# smarthome-agent-1.net
KiCad netlist of a schematic drawn in EAGLE
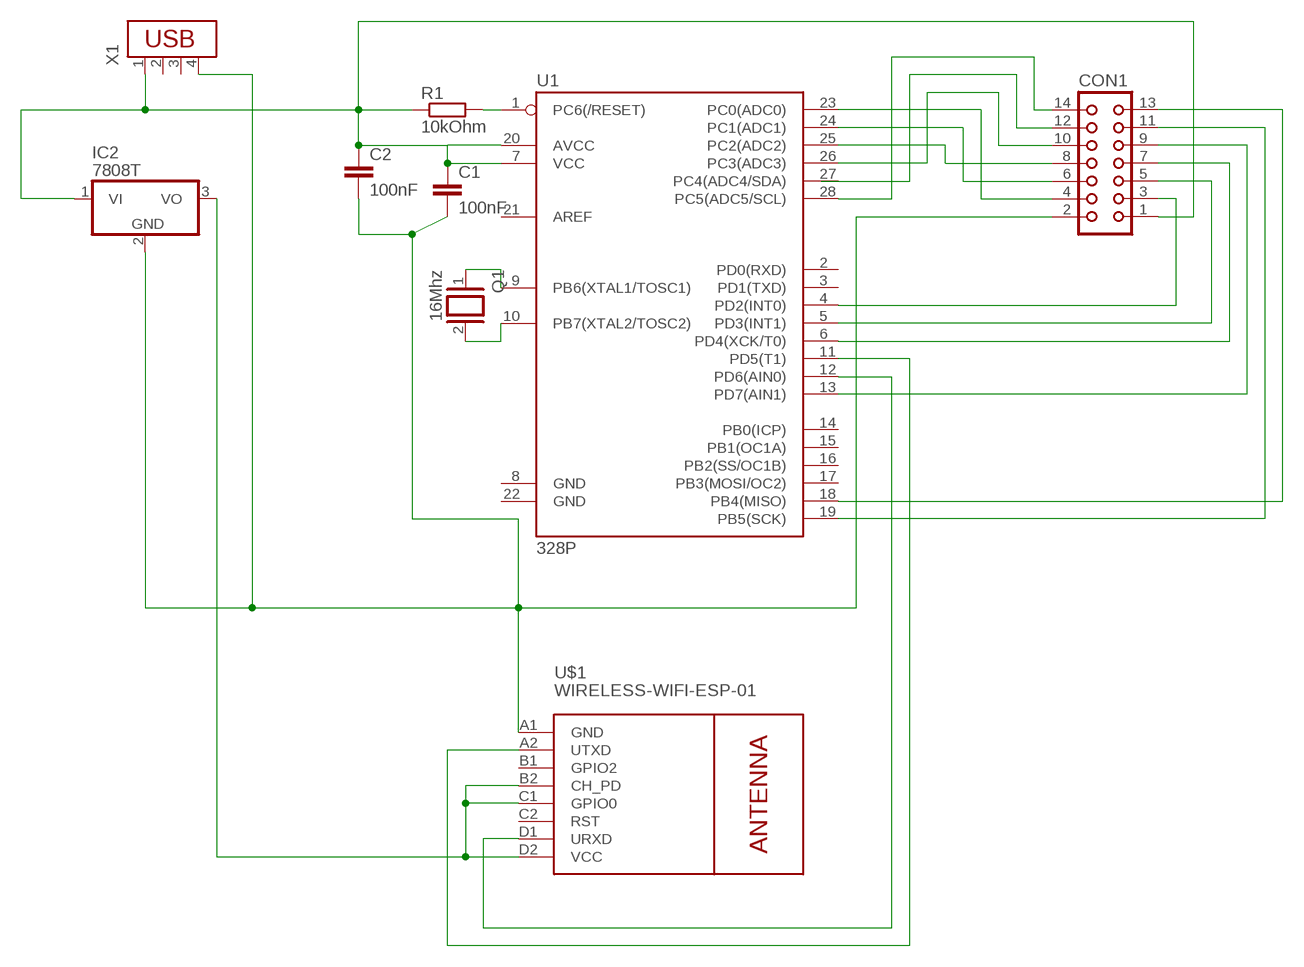
[diagram p0: schematic, sheet 1]

(export (version "E")
  (design (tool "Eeschema 10.0.6"))
  (components
    (comp (ref "C1")
      (value "100nF")
      (footprint "eagle-import:C025-024X044")
      (libsource (lib "eagle-import") (part "C-EU025-024X044"))
    )
    (comp (ref "C2")
      (value "100nF")
      (footprint "eagle-import:C025-024X044")
      (libsource (lib "eagle-import") (part "C-EU025-024X044"))
    )
    (comp (ref "CON1")
      (value "CON14")
      (footprint "eagle-import:CON14")
      (libsource (lib "eagle-import") (part "CON14"))
    )
    (comp (ref "IC2")
      (value "7808T")
      (footprint "eagle-import:TO220H")
      (libsource (lib "eagle-import") (part "78T08"))
    )
    (comp (ref "Q1")
      (value "16Mhz")
      (footprint "eagle-import:QS")
      (libsource (lib "eagle-import") (part "XTAL/S"))
    )
    (comp (ref "R1")
      (value "10kOhm")
      (footprint "eagle-import:0204_7")
      (libsource (lib "eagle-import") (part "R-EU_0204/7"))
    )
    (comp (ref "U$1")
      (value "WIRELESS-WIFI-ESP-01")
      (footprint "eagle-import:WIRELESS-WIFI-ESP-01")
      (libsource (lib "eagle-import") (part "WIRELESS-WIFI-ESP-01"))
    )
    (comp (ref "U1")
      (value "328P")
      (footprint "eagle-import:DIP28")
      (libsource (lib "eagle-import") (part "ATMEGA328P_PDIP"))
    )
    (comp (ref "X1")
      (value "USB-787616")
      (footprint "eagle-import:USB")
      (libsource (lib "eagle-import") (part "USB-787616"))
    )
  )
  (nets
    (net (code "1") (name "Net-(IC2-GND)") (class "Default")
      (node (ref "C1") (pin "2") (pinfunction "2_2") (pintype "passive"))
      (node (ref "C2") (pin "2") (pinfunction "2_2") (pintype "passive"))
      (node (ref "CON1") (pin "2") (pinfunction "2_2") (pintype "passive"))
      (node (ref "IC2") (pin "2") (pinfunction "GND_2") (pintype "passive"))
      (node (ref "U$1") (pin "A1") (pinfunction "GND_A1") (pintype "power_in"))
      (node (ref "X1") (pin "4") (pinfunction "4_4") (pintype "passive"))
    )
    (net (code "2") (name "Net-(IC2-VI)") (class "Default")
      (node (ref "C1") (pin "1") (pinfunction "1_1") (pintype "passive"))
      (node (ref "C2") (pin "1") (pinfunction "1_1") (pintype "passive"))
      (node (ref "CON1") (pin "1") (pinfunction "1_1") (pintype "passive"))
      (node (ref "IC2") (pin "1") (pinfunction "VI_1") (pintype "input"))
      (node (ref "R1") (pin "1") (pinfunction "1_1") (pintype "passive"))
      (node (ref "U1") (pin "20") (pinfunction "AVCC_20") (pintype "bidirectional"))
      (node (ref "U1") (pin "7") (pinfunction "VCC_7") (pintype "bidirectional"))
      (node (ref "X1") (pin "1") (pinfunction "1_1") (pintype "passive"))
    )
    (net (code "3") (name "Net-(IC2-VO)") (class "Default")
      (node (ref "IC2") (pin "3") (pinfunction "VO_3") (pintype "passive"))
      (node (ref "U$1") (pin "B2") (pinfunction "CH_PD_B2") (pintype "bidirectional"))
      (node (ref "U$1") (pin "C1") (pinfunction "GPIO0_C1") (pintype "bidirectional"))
      (node (ref "U$1") (pin "D2") (pinfunction "VCC_D2") (pintype "power_in"))
    )
    (net (code "4") (name "Net-(U$1-URXD)") (class "Default")
      (node (ref "U$1") (pin "D1") (pinfunction "URXD_D1") (pintype "bidirectional"))
      (node (ref "U1") (pin "12") (pinfunction "PD6(AIN0)_12") (pintype "bidirectional"))
    )
    (net (code "5") (name "Net-(U$1-UTXD)") (class "Default")
      (node (ref "U$1") (pin "A2") (pinfunction "UTXD_A2") (pintype "bidirectional"))
      (node (ref "U1") (pin "11") (pinfunction "PD5(T1)_11") (pintype "bidirectional"))
    )
    (net (code "6") (name "Net-(U1-PB4(MISO))") (class "Default")
      (node (ref "CON1") (pin "13") (pinfunction "13_13") (pintype "passive"))
      (node (ref "U1") (pin "18") (pinfunction "PB4(MISO)_18") (pintype "bidirectional"))
    )
    (net (code "7") (name "Net-(U1-PB5(SCK))") (class "Default")
      (node (ref "CON1") (pin "11") (pinfunction "11_11") (pintype "passive"))
      (node (ref "U1") (pin "19") (pinfunction "PB5(SCK)_19") (pintype "bidirectional"))
    )
    (net (code "8") (name "Net-(U1-PB6(XTAL1{slash}TOSC1))") (class "Default")
      (node (ref "Q1") (pin "1") (pinfunction "1_1") (pintype "passive"))
      (node (ref "U1") (pin "9") (pinfunction "PB6(XTAL1/TOSC1)_9") (pintype "bidirectional"))
    )
    (net (code "9") (name "Net-(U1-PB7(XTAL2{slash}TOSC2))") (class "Default")
      (node (ref "Q1") (pin "2") (pinfunction "2_2") (pintype "passive"))
      (node (ref "U1") (pin "10") (pinfunction "PB7(XTAL2/TOSC2)_10") (pintype "bidirectional"))
    )
    (net (code "10") (name "Net-(U1-PC0(ADC0))") (class "Default")
      (node (ref "CON1") (pin "4") (pinfunction "4_4") (pintype "passive"))
      (node (ref "U1") (pin "23") (pinfunction "PC0(ADC0)_23") (pintype "bidirectional"))
    )
    (net (code "11") (name "Net-(U1-PC1(ADC1))") (class "Default")
      (node (ref "CON1") (pin "6") (pinfunction "6_6") (pintype "passive"))
      (node (ref "U1") (pin "24") (pinfunction "PC1(ADC1)_24") (pintype "bidirectional"))
    )
    (net (code "12") (name "Net-(U1-PC2(ADC2))") (class "Default")
      (node (ref "CON1") (pin "8") (pinfunction "8_8") (pintype "passive"))
      (node (ref "U1") (pin "25") (pinfunction "PC2(ADC2)_25") (pintype "bidirectional"))
    )
    (net (code "13") (name "Net-(U1-PC3(ADC3))") (class "Default")
      (node (ref "CON1") (pin "10") (pinfunction "10_10") (pintype "passive"))
      (node (ref "U1") (pin "26") (pinfunction "PC3(ADC3)_26") (pintype "bidirectional"))
    )
    (net (code "14") (name "Net-(U1-PC4(ADC4{slash}SDA))") (class "Default")
      (node (ref "CON1") (pin "12") (pinfunction "12_12") (pintype "passive"))
      (node (ref "U1") (pin "27") (pinfunction "PC4(ADC4/SDA)_27") (pintype "bidirectional"))
    )
    (net (code "15") (name "Net-(U1-PC5(ADC5{slash}SCL))") (class "Default")
      (node (ref "CON1") (pin "14") (pinfunction "14_14") (pintype "passive"))
      (node (ref "U1") (pin "28") (pinfunction "PC5(ADC5/SCL)_28") (pintype "bidirectional"))
    )
    (net (code "16") (name "Net-(U1-PC6({slash}RESET))") (class "Default")
      (node (ref "R1") (pin "2") (pinfunction "2_2") (pintype "passive"))
      (node (ref "U1") (pin "1") (pinfunction "PC6(/RESET)_1") (pintype "bidirectional"))
    )
    (net (code "17") (name "Net-(U1-PD2(INT0))") (class "Default")
      (node (ref "CON1") (pin "3") (pinfunction "3_3") (pintype "passive"))
      (node (ref "U1") (pin "4") (pinfunction "PD2(INT0)_4") (pintype "bidirectional"))
    )
    (net (code "18") (name "Net-(U1-PD3(INT1))") (class "Default")
      (node (ref "CON1") (pin "5") (pinfunction "5_5") (pintype "passive"))
      (node (ref "U1") (pin "5") (pinfunction "PD3(INT1)_5") (pintype "bidirectional"))
    )
    (net (code "19") (name "Net-(U1-PD4(XCK{slash}T0))") (class "Default")
      (node (ref "CON1") (pin "7") (pinfunction "7_7") (pintype "passive"))
      (node (ref "U1") (pin "6") (pinfunction "PD4(XCK/T0)_6") (pintype "bidirectional"))
    )
    (net (code "20") (name "Net-(U1-PD7(AIN1))") (class "Default")
      (node (ref "CON1") (pin "9") (pinfunction "9_9") (pintype "passive"))
      (node (ref "U1") (pin "13") (pinfunction "PD7(AIN1)_13") (pintype "bidirectional"))
    )
    (net (code "21") (name "unconnected-(U$1-GPIO2-PadB1)") (class "Default")
      (node (ref "U$1") (pin "B1") (pinfunction "GPIO2_B1") (pintype "bidirectional"))
    )
    (net (code "22") (name "unconnected-(U$1-RST-PadC2)") (class "Default")
      (node (ref "U$1") (pin "C2") (pinfunction "RST_C2") (pintype "bidirectional"))
    )
    (net (code "23") (name "unconnected-(U1-AREF-Pad21)") (class "Default")
      (node (ref "U1") (pin "21") (pinfunction "AREF_21") (pintype "bidirectional"))
    )
    (net (code "24") (name "unconnected-(U1-GND-Pad8)") (class "Default")
      (node (ref "U1") (pin "8") (pinfunction "GND_8") (pintype "bidirectional"))
    )
    (net (code "25") (name "unconnected-(U1-GND-Pad22)") (class "Default")
      (node (ref "U1") (pin "22") (pinfunction "GND_22") (pintype "bidirectional"))
    )
    (net (code "26") (name "unconnected-(U1-PB0(ICP)-Pad14)") (class "Default")
      (node (ref "U1") (pin "14") (pinfunction "PB0(ICP)_14") (pintype "bidirectional"))
    )
    (net (code "27") (name "unconnected-(U1-PB1(OC1A)-Pad15)") (class "Default")
      (node (ref "U1") (pin "15") (pinfunction "PB1(OC1A)_15") (pintype "bidirectional"))
    )
    (net (code "28") (name "unconnected-(U1-PB2(SS{slash}OC1B)-Pad16)") (class "Default")
      (node (ref "U1") (pin "16") (pinfunction "PB2(SS/OC1B)_16") (pintype "bidirectional"))
    )
    (net (code "29") (name "unconnected-(U1-PB3(MOSI{slash}OC2)-Pad17)") (class "Default")
      (node (ref "U1") (pin "17") (pinfunction "PB3(MOSI/OC2)_17") (pintype "bidirectional"))
    )
    (net (code "30") (name "unconnected-(U1-PD0(RXD)-Pad2)") (class "Default")
      (node (ref "U1") (pin "2") (pinfunction "PD0(RXD)_2") (pintype "bidirectional"))
    )
    (net (code "31") (name "unconnected-(U1-PD1(TXD)-Pad3)") (class "Default")
      (node (ref "U1") (pin "3") (pinfunction "PD1(TXD)_3") (pintype "bidirectional"))
    )
    (net (code "32") (name "unconnected-(X1-Pad2)") (class "Default")
      (node (ref "X1") (pin "2") (pinfunction "2_2") (pintype "passive"))
    )
    (net (code "33") (name "unconnected-(X1-Pad3)") (class "Default")
      (node (ref "X1") (pin "3") (pinfunction "3_3") (pintype "passive"))
    )
  )
)
